# MARS_PORB.net
KiCad netlist of a schematic drawn in Altium Designer
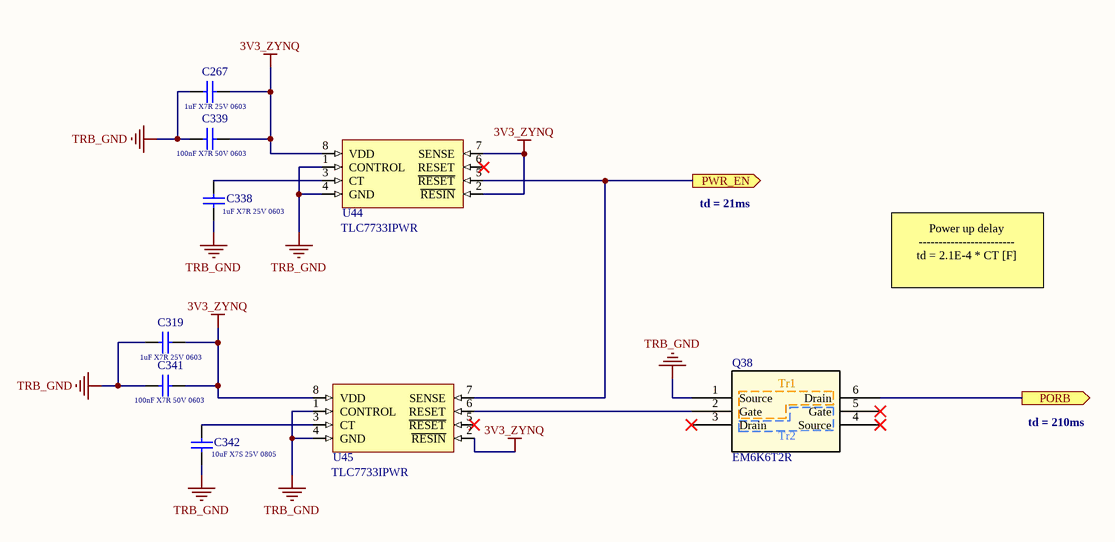
[diagram p0: MARS_PORB.SchDoc]

(export (version "E")
  (design (tool "Eeschema 10.0.6"))
  (components
    (comp (ref "C267")
      (value "Cap_Murata_GCJ188R71E105KA01J_1uF")
      (footprint "Cap_Murata_GCJ188R71E105KA01J_1uF")
      (description "CAP CER 1uF 25V X7R 0603")
      (fields (field (name "CAPACITANCE") "1uF X7R 25V 0603"))
      (libsource (lib "Cap_Murata_GCJ188R71E105KA01J_1uF") (part "Cap_Murata_GCJ188R71E105KA01J_1uF"))
    )
    (comp (ref "C319")
      (value "Cap_Murata_GCJ188R71E105KA01J_1uF")
      (footprint "Cap_Murata_GCJ188R71E105KA01J_1uF")
      (description "CAP CER 1uF 25V X7R 0603")
      (fields (field (name "CAPACITANCE") "1uF X7R 25V 0603"))
      (libsource (lib "Cap_Murata_GCJ188R71E105KA01J_1uF") (part "Cap_Murata_GCJ188R71E105KA01J_1uF"))
    )
    (comp (ref "C338")
      (value "Cap_Murata_GCJ188R71E105KA01J_1uF")
      (footprint "Cap_Murata_GCJ188R71E105KA01J_1uF")
      (description "CAP CER 1uF 25V X7R 0603")
      (fields (field (name "CAPACITANCE") "1uF X7R 25V 0603"))
      (libsource (lib "Cap_Murata_GCJ188R71E105KA01J_1uF") (part "Cap_Murata_GCJ188R71E105KA01J_1uF"))
    )
    (comp (ref "C339")
      (value "Cap_Kemet_C0603C104M5RACAUTO_100nF")
      (footprint "Cap_Kemet_C0603C104M5RACAUTO_100nF")
      (description "CAP CER 100nF 50V X7R 0603")
      (fields (field (name "CAPACITANCE") "100nF X7R 50V 0603"))
      (libsource (lib "Cap_Kemet_C0603C104M5RACAUTO_100nF") (part "Cap_Kemet_C0603C104M5RACAUTO_100nF"))
    )
    (comp (ref "C341")
      (value "Cap_Kemet_C0603C104M5RACAUTO_100nF")
      (footprint "Cap_Kemet_C0603C104M5RACAUTO_100nF")
      (description "CAP CER 100nF 50V X7R 0603")
      (fields (field (name "CAPACITANCE") "100nF X7R 50V 0603"))
      (libsource (lib "Cap_Kemet_C0603C104M5RACAUTO_100nF") (part "Cap_Kemet_C0603C104M5RACAUTO_100nF"))
    )
    (comp (ref "C342")
      (value "Cap_Murata_ GRM21BC71E106ME11L_10uF")
      (footprint "Cap_Murata_ GRM21BC71E106ME11L_10uF")
      (description "CAP CER 10uF 25V X7R 0805")
      (fields (field (name "CAPACITANCE") "10uF X7S 25V 0805"))
      (libsource (lib "Cap_Murata_ GRM21BC71E106ME11L_10uF") (part "Cap_Murata_ GRM21BC71E106ME11L_10uF"))
    )
    (comp (ref "Q38")
      (value "EM6K6T2R")
      (footprint "TRANS_EM6_ROM")
      (description "MOSFET Small Signal Dual N-CH 20V .3A .15W")
      (libsource (lib "Trans_NFET_ROHM_EM6K6T2R") (part "EM6K6T2R"))
    )
    (comp (ref "U44")
      (value "TLC7733IPWR")
      (footprint "PMU_Texas_Instruments_TLC7733IPWR_2.93")
      (description "Supervisory Circuits 2.93V Monitor")
      (libsource (lib "PMU_Texas_Instruments_TLC7733IPWR_2.93") (part "PMU_Texas_Instruments_TLC7733IPWR_2.93"))
    )
    (comp (ref "U45")
      (value "TLC7733IPWR")
      (footprint "PMU_Texas_Instruments_TLC7733IPWR_2.93")
      (description "Supervisory Circuits 2.93V Monitor")
      (libsource (lib "PMU_Texas_Instruments_TLC7733IPWR_2.93") (part "PMU_Texas_Instruments_TLC7733IPWR_2.93"))
    )
  )
  (nets
    (net (code "1") (name "/PORB") (class "Default")
      (node (ref "Q38") (pin "6") (pinfunction "Drain_6") (pintype "passive"))
    )
    (net (code "2") (name "/PWR_EN") (class "Default")
      (node (ref "U44") (pin "5") (pinfunction "~{RESET}_5") (pintype "input"))
      (node (ref "U45") (pin "7") (pinfunction "SENSE_7") (pintype "input"))
    )
    (net (code "3") (name "3V3_ZYNQ") (class "Default")
      (node (ref "C267") (pin "1") (pinfunction "1_1") (pintype "passive"))
      (node (ref "C319") (pin "1") (pinfunction "1_1") (pintype "passive"))
      (node (ref "C339") (pin "1") (pinfunction "1_1") (pintype "passive"))
      (node (ref "C341") (pin "1") (pinfunction "1_1") (pintype "passive"))
      (node (ref "U44") (pin "2") (pinfunction "~{RESIN}_2") (pintype "input"))
      (node (ref "U44") (pin "7") (pinfunction "SENSE_7") (pintype "input"))
      (node (ref "U44") (pin "8") (pinfunction "VDD_8") (pintype "input"))
      (node (ref "U45") (pin "2") (pinfunction "~{RESIN}_2") (pintype "input"))
      (node (ref "U45") (pin "8") (pinfunction "VDD_8") (pintype "input"))
    )
    (net (code "4") (name "Net-(U44-CT)") (class "Default")
      (node (ref "C338") (pin "2") (pinfunction "2_2") (pintype "passive"))
      (node (ref "U44") (pin "3") (pinfunction "CT_3") (pintype "input"))
    )
    (net (code "5") (name "Net-(U45-CT)") (class "Default")
      (node (ref "C342") (pin "1") (pinfunction "1_1") (pintype "passive"))
      (node (ref "U45") (pin "3") (pinfunction "CT_3") (pintype "input"))
    )
    (net (code "6") (name "Net-(U45-RESET)") (class "Default")
      (node (ref "Q38") (pin "2") (pinfunction "Gate_2") (pintype "passive"))
      (node (ref "U45") (pin "6") (pinfunction "RESET_6") (pintype "input"))
    )
    (net (code "7") (name "TRB_GND") (class "Default")
      (node (ref "C267") (pin "2") (pinfunction "2_2") (pintype "passive"))
      (node (ref "C319") (pin "2") (pinfunction "2_2") (pintype "passive"))
      (node (ref "C338") (pin "1") (pinfunction "1_1") (pintype "passive"))
      (node (ref "C339") (pin "2") (pinfunction "2_2") (pintype "passive"))
      (node (ref "C341") (pin "2") (pinfunction "2_2") (pintype "passive"))
      (node (ref "C342") (pin "2") (pinfunction "2_2") (pintype "passive"))
      (node (ref "Q38") (pin "1") (pinfunction "Source_1") (pintype "passive"))
      (node (ref "U44") (pin "1") (pinfunction "CONTROL_1") (pintype "input"))
      (node (ref "U44") (pin "4") (pinfunction "GND_4") (pintype "input"))
      (node (ref "U45") (pin "1") (pinfunction "CONTROL_1") (pintype "input"))
      (node (ref "U45") (pin "4") (pinfunction "GND_4") (pintype "input"))
    )
    (net (code "8") (name "unconnected-(Q38-Drain-Pad3)") (class "Default")
      (node (ref "Q38") (pin "3") (pinfunction "Drain_3") (pintype "passive+no_connect"))
    )
    (net (code "9") (name "unconnected-(Q38-Gate-Pad5)") (class "Default")
      (node (ref "Q38") (pin "5") (pinfunction "Gate_5") (pintype "passive+no_connect"))
    )
    (net (code "10") (name "unconnected-(Q38-Source-Pad4)") (class "Default")
      (node (ref "Q38") (pin "4") (pinfunction "Source_4") (pintype "passive+no_connect"))
    )
    (net (code "11") (name "unconnected-(U44-RESET-Pad6)") (class "Default")
      (node (ref "U44") (pin "6") (pinfunction "RESET_6") (pintype "input+no_connect"))
    )
    (net (code "12") (name "unconnected-(U45-~{RESET}-Pad5)") (class "Default")
      (node (ref "U45") (pin "5") (pinfunction "~{RESET}_5") (pintype "input+no_connect"))
    )
  )
)
